# Schematic-easyEda.net
KiCad netlist of a schematic drawn in EasyEDA
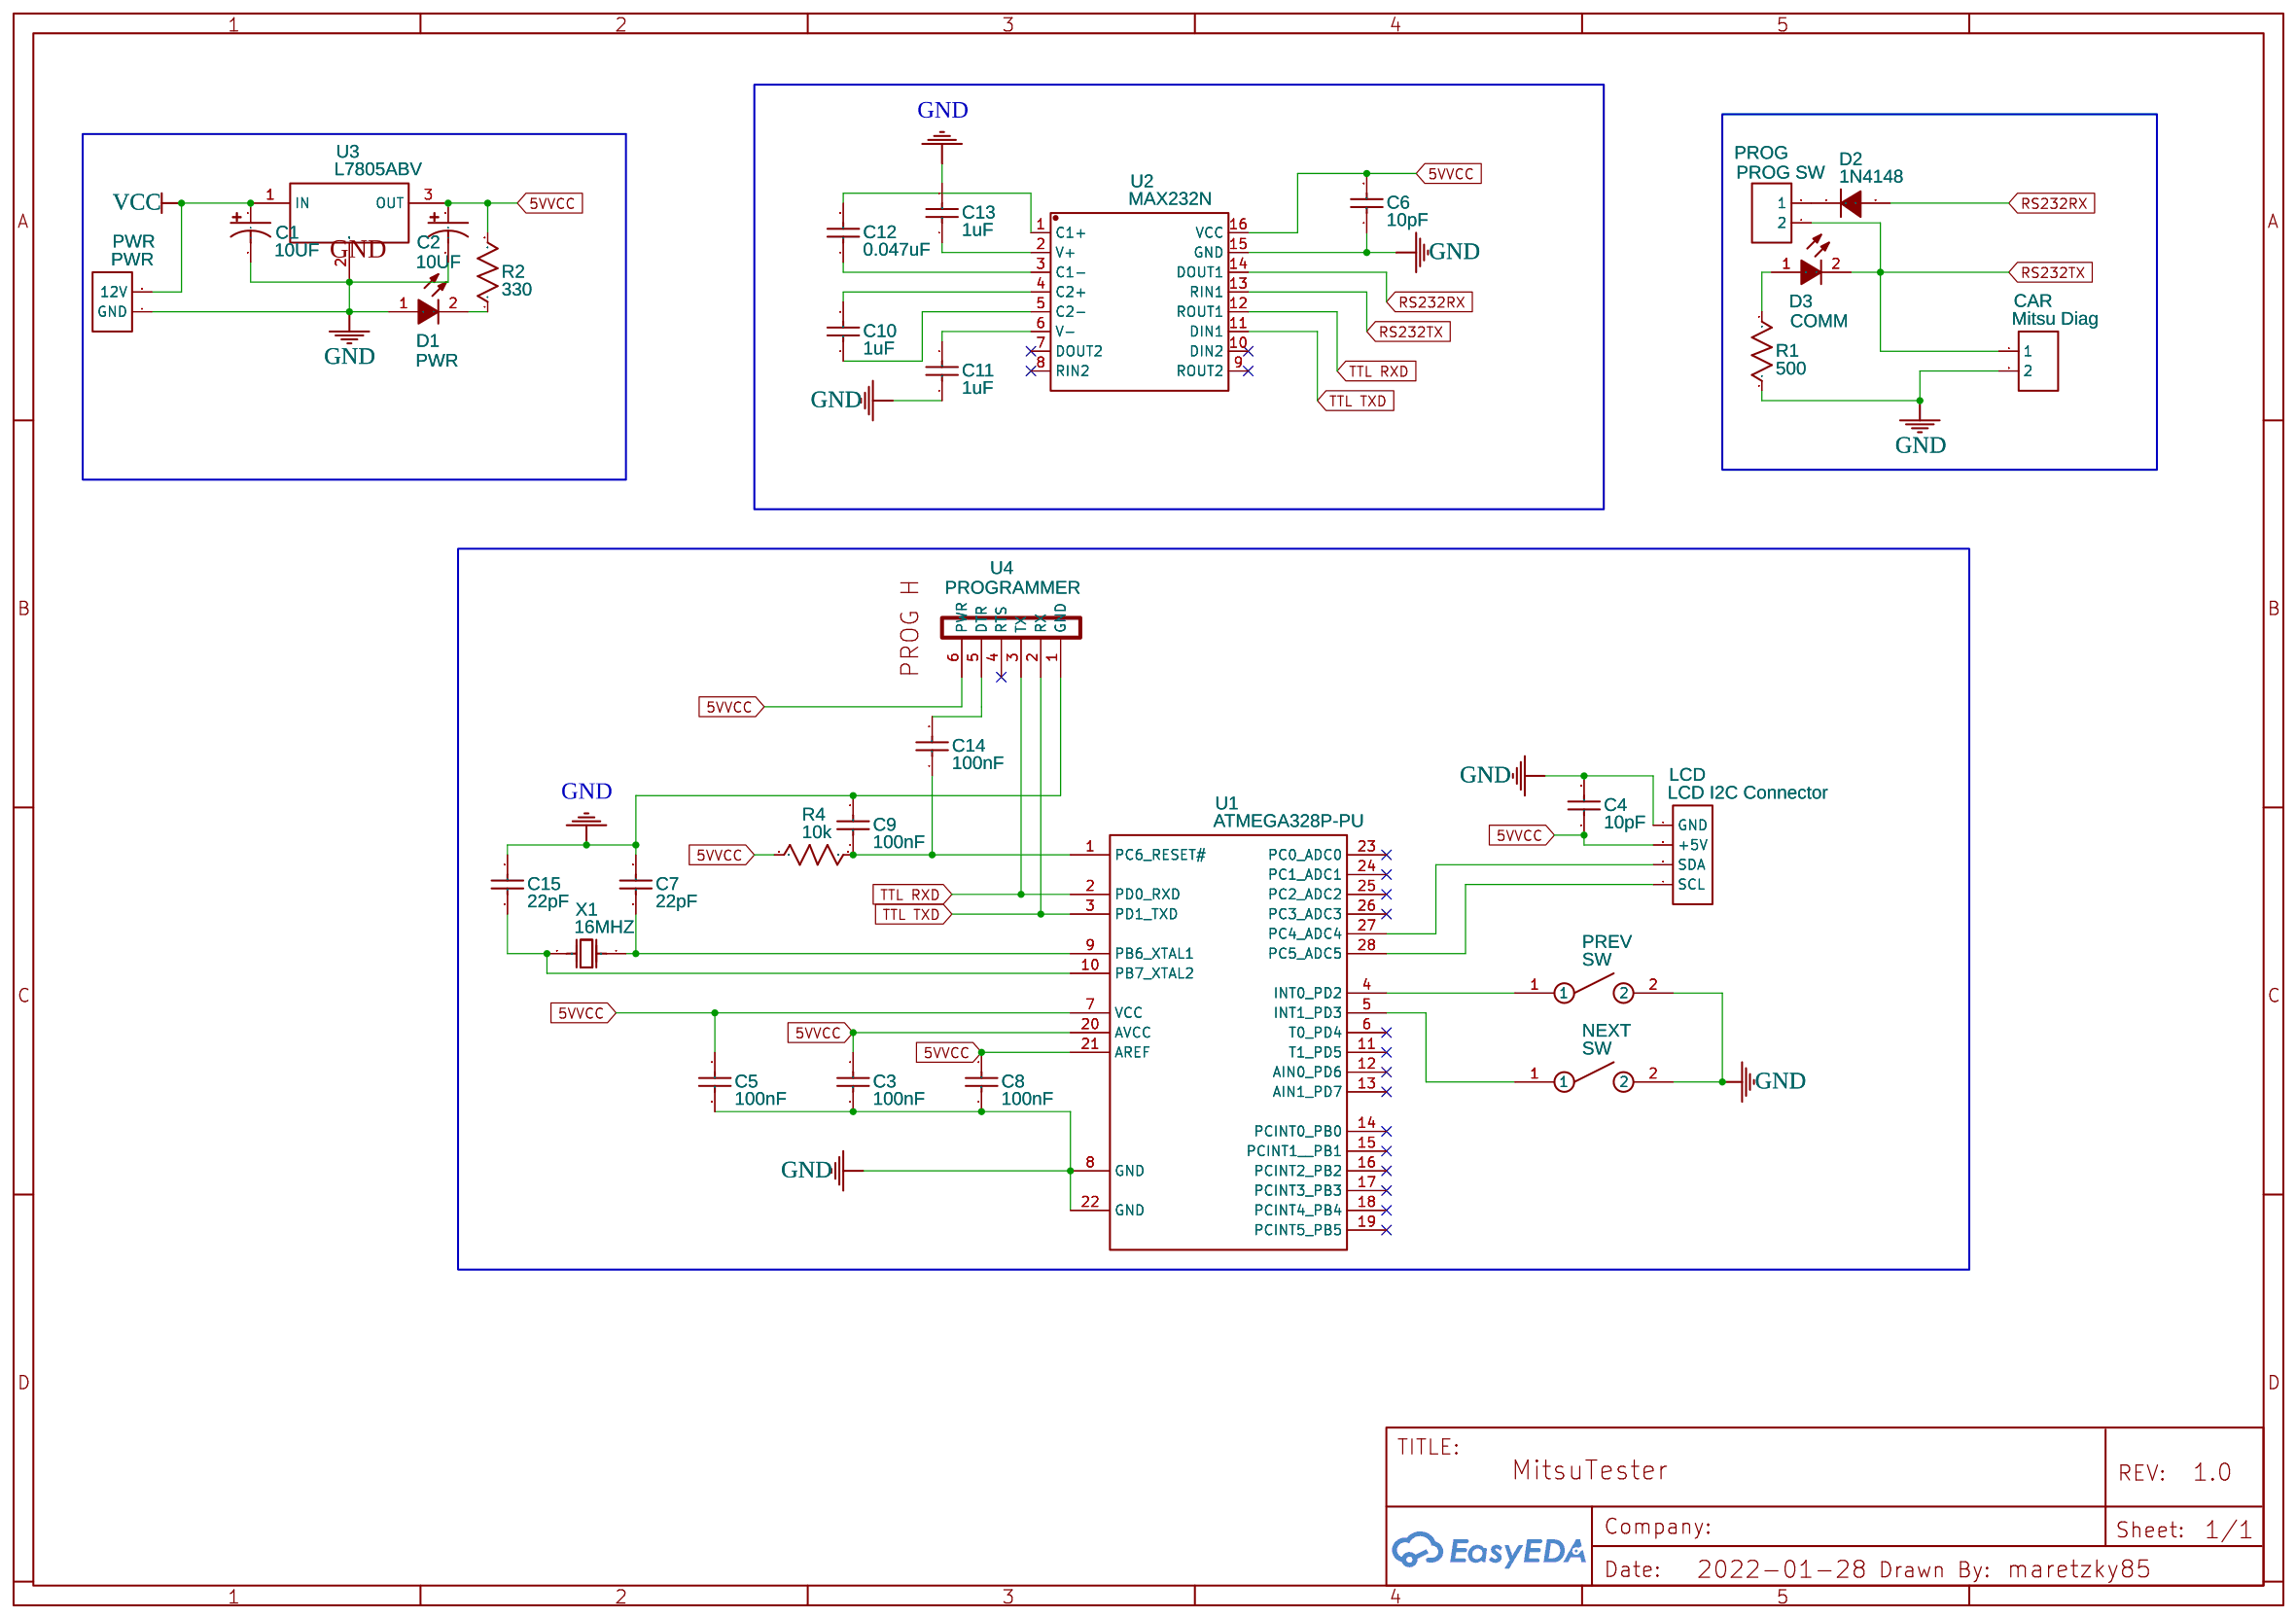
[diagram p0: schematic sheet]

(export (version "E")
  (design (tool "Eeschema 10.0.6"))
  (components
    (comp (ref "C1") (value "10UF") (libsource (lib "") (part "10UF-25V-20%(PTH)KIT")))
    (comp (ref "C2") (value "10UF") (libsource (lib "") (part "10UF-25V-20%(PTH)KIT")))
    (comp (ref "C3")
      (value "100nF")
      (fields
        (field (name "BOM_Manufacturer Part") "0.01 25V Ceramic capacitor")
        (field (name "BOM_Supplier Part") "C22320")
      )
      (libsource (lib "") (part "0.01 25V Ceramic capacitor"))
    )
    (comp (ref "C4")
      (value "10pF")
      (fields
        (field (name "BOM_Manufacturer Part") "0.01 25V Ceramic capacitor")
        (field (name "BOM_Supplier Part") "C22320")
      )
      (libsource (lib "") (part "0.01 25V Ceramic capacitor"))
    )
    (comp (ref "C5")
      (value "100nF")
      (fields
        (field (name "BOM_Manufacturer Part") "0.01 25V Ceramic capacitor")
        (field (name "BOM_Supplier Part") "C22320")
      )
      (libsource (lib "") (part "0.01 25V Ceramic capacitor"))
    )
    (comp (ref "C6")
      (value "10pF")
      (fields
        (field (name "BOM_Manufacturer Part") "0.01 25V Ceramic capacitor")
        (field (name "BOM_Supplier Part") "C22320")
      )
      (libsource (lib "") (part "0.01 25V Ceramic capacitor"))
    )
    (comp (ref "C7")
      (value "22pF")
      (fields
        (field (name "BOM_Manufacturer Part") "0.01 25V Ceramic capacitor")
        (field (name "BOM_Supplier Part") "C22320")
      )
      (libsource (lib "") (part "0.01 25V Ceramic capacitor"))
    )
    (comp (ref "C8")
      (value "100nF")
      (fields
        (field (name "BOM_Manufacturer Part") "0.01 25V Ceramic capacitor")
        (field (name "BOM_Supplier Part") "C22320")
      )
      (libsource (lib "") (part "0.01 25V Ceramic capacitor"))
    )
    (comp (ref "C9")
      (value "100nF")
      (fields
        (field (name "BOM_Manufacturer Part") "0.01 25V Ceramic capacitor")
        (field (name "BOM_Supplier Part") "C22320")
      )
      (libsource (lib "") (part "0.01 25V Ceramic capacitor"))
    )
    (comp (ref "C10")
      (value "1uF")
      (fields
        (field (name "BOM_Manufacturer Part") "0.01 25V Ceramic capacitor")
        (field (name "BOM_Supplier Part") "C22320")
      )
      (libsource (lib "") (part "0.01 25V Ceramic capacitor"))
    )
    (comp (ref "C11")
      (value "1uF")
      (fields
        (field (name "BOM_Manufacturer Part") "0.01 25V Ceramic capacitor")
        (field (name "BOM_Supplier Part") "C22320")
      )
      (libsource (lib "") (part "0.01 25V Ceramic capacitor"))
    )
    (comp (ref "C12")
      (value "0.047uF")
      (fields
        (field (name "BOM_Manufacturer Part") "0.01 25V Ceramic capacitor")
        (field (name "BOM_Supplier Part") "C22320")
      )
      (libsource (lib "") (part "0.01 25V Ceramic capacitor"))
    )
    (comp (ref "C13")
      (value "1uF")
      (fields
        (field (name "BOM_Manufacturer Part") "0.01 25V Ceramic capacitor")
        (field (name "BOM_Supplier Part") "C22320")
      )
      (libsource (lib "") (part "0.01 25V Ceramic capacitor"))
    )
    (comp (ref "C14")
      (value "100nF")
      (fields
        (field (name "BOM_Manufacturer Part") "0.01 25V Ceramic capacitor")
        (field (name "BOM_Supplier Part") "C22320")
      )
      (libsource (lib "") (part "0.01 25V Ceramic capacitor"))
    )
    (comp (ref "C15")
      (value "22pF")
      (fields
        (field (name "BOM_Manufacturer Part") "0.01 25V Ceramic capacitor")
        (field (name "BOM_Supplier Part") "C22320")
      )
      (libsource (lib "") (part "0.01 25V Ceramic capacitor"))
    )
    (comp (ref "CAR")
      (value "Mitsu Diag")
      (fields (field (name "BOM_Supplier Part") "C49661"))
      (libsource (lib "") (part "HDR-F-2.54_1x2_2"))
    )
    (comp (ref "D1")
      (value "PWR")
      (fields (field (name "BOM_Manufacturer Part") "5600") (field (name "BOM_Supplier Part") "L20325-ND"))
      (libsource (lib "") (part "3mm Green TH LED 5600"))
    )
    (comp (ref "D2")
      (value "1N4148")
      (fields (field (name "BOM_Manufacturer Part") "1N4007") (field (name "BOM_Supplier Part") "C106903"))
      (libsource (lib "") (part "2.54_DUMMY_DIODE"))
    )
    (comp (ref "D3")
      (value "COMM")
      (fields (field (name "BOM_Manufacturer Part") "5600") (field (name "BOM_Supplier Part") "L20325-ND"))
      (libsource (lib "") (part "3mm Green TH LED 5600"))
    )
    (comp (ref "LCD")
      (value "LCD I2C Connector")
      (fields (field (name "BOM_Supplier Part") "C225501"))
      (libsource (lib "") (part "HDR-F-2.54_1x4"))
    )
    (comp (ref "NEXT") (value "SW") (libsource (lib "") (part "SW_1")))
    (comp (ref "PREV") (value "SW") (libsource (lib "") (part "SW")))
    (comp (ref "PROG")
      (value "PROG SW")
      (fields (field (name "BOM_Supplier Part") "C49661"))
      (libsource (lib "") (part "HDR-F-2.54_1x2"))
    )
    (comp (ref "PWR")
      (value "PWR")
      (fields (field (name "BOM_Supplier Part") "C49661"))
      (libsource (lib "") (part "HDR-F-2.54_1x2_1"))
    )
    (comp (ref "R1") (value "500") (libsource (lib "") (part "R_AXIAL-0.3_US")))
    (comp (ref "R2") (value "330") (libsource (lib "") (part "R_AXIAL-0.3_US")))
    (comp (ref "R4") (value "10k") (libsource (lib "") (part "R_AXIAL-0.3_US_1")))
    (comp (ref "U1")
      (value "ATMEGA328P-PU")
      (fields (field (name "BOM_Supplier Part") "C33901"))
      (libsource (lib "") (part "ATMEGA328P-PU"))
    )
    (comp (ref "U2")
      (value "MAX232N")
      (fields (field (name "BOM_Supplier Part") "C353147"))
      (libsource (lib "") (part "MAX232N"))
    )
    (comp (ref "U3")
      (value "L7805ABV")
      (fields (field (name "BOM_Supplier Part") "C16807"))
      (libsource (lib "") (part "L7805ABV"))
    )
    (comp (ref "U4") (value "PROGRAMMER") (libsource (lib "") (part "6Pin Sip Header")))
    (comp (ref "X1")
      (value "16MHZ")
      (fields
        (field (name "BOM_Manufacturer Part") "49SAC16000202060")
        (field (name "BOM_Supplier Part") "C390745")
      )
      (libsource (lib "") (part "CRYSTAL 16MHZ"))
    )
  )
  (nets
    (net (code "1") (name "5VVCC") (class "Default")
      (node (ref "C2") (pin "1") (pinfunction "+_1") (pintype "unspecified"))
      (node (ref "C3") (pin "2") (pinfunction "2_2") (pintype "input"))
      (node (ref "C4") (pin "1") (pinfunction "1_1") (pintype "input"))
      (node (ref "C5") (pin "2") (pinfunction "2_2") (pintype "input"))
      (node (ref "C6") (pin "2") (pinfunction "2_2") (pintype "input"))
      (node (ref "C8") (pin "2") (pinfunction "2_2") (pintype "input"))
      (node (ref "LCD") (pin "2") (pinfunction "+5V_2") (pintype "unspecified"))
      (node (ref "R2") (pin "2") (pinfunction "2_2") (pintype "unspecified"))
      (node (ref "R4") (pin "1") (pinfunction "1_1") (pintype "unspecified"))
      (node (ref "U1") (pin "20") (pinfunction "AVCC_20") (pintype "passive"))
      (node (ref "U1") (pin "21") (pinfunction "AREF_21") (pintype "passive"))
      (node (ref "U1") (pin "7") (pinfunction "VCC_7") (pintype "passive"))
      (node (ref "U2") (pin "16") (pinfunction "VCC_16") (pintype "unspecified"))
      (node (ref "U3") (pin "3") (pinfunction "OUT_3") (pintype "passive"))
      (node (ref "U4") (pin "6") (pinfunction "PWR_6") (pintype "unspecified"))
    )
    (net (code "2") (name "GND") (class "Default")
      (node (ref "C1") (pin "2") (pinfunction "-_2") (pintype "unspecified"))
      (node (ref "C11") (pin "1") (pinfunction "1_1") (pintype "input"))
      (node (ref "C13") (pin "2") (pinfunction "2_2") (pintype "input"))
      (node (ref "C15") (pin "2") (pinfunction "2_2") (pintype "input"))
      (node (ref "C2") (pin "2") (pinfunction "-_2") (pintype "unspecified"))
      (node (ref "C3") (pin "1") (pinfunction "1_1") (pintype "input"))
      (node (ref "C4") (pin "2") (pinfunction "2_2") (pintype "input"))
      (node (ref "C5") (pin "1") (pinfunction "1_1") (pintype "input"))
      (node (ref "C6") (pin "1") (pinfunction "1_1") (pintype "input"))
      (node (ref "C7") (pin "2") (pinfunction "2_2") (pintype "input"))
      (node (ref "C8") (pin "1") (pinfunction "1_1") (pintype "input"))
      (node (ref "C9") (pin "2") (pinfunction "2_2") (pintype "input"))
      (node (ref "CAR") (pin "2") (pinfunction "2_2") (pintype "input"))
      (node (ref "D1") (pin "1") (pinfunction "A_1") (pintype "unspecified"))
      (node (ref "LCD") (pin "1") (pinfunction "GND_1") (pintype "unspecified"))
      (node (ref "NEXT") (pin "2") (pinfunction "2_2") (pintype "unspecified"))
      (node (ref "PREV") (pin "2") (pinfunction "2_2") (pintype "unspecified"))
      (node (ref "PWR") (pin "1") (pinfunction "GND_1") (pintype "input"))
      (node (ref "R1") (pin "1") (pinfunction "1_1") (pintype "unspecified"))
      (node (ref "U1") (pin "22") (pinfunction "GND_22") (pintype "passive"))
      (node (ref "U1") (pin "8") (pinfunction "GND_8") (pintype "passive"))
      (node (ref "U2") (pin "15") (pinfunction "GND_15") (pintype "unspecified"))
      (node (ref "U3") (pin "2") (pinfunction "GND_2") (pintype "passive"))
      (node (ref "U4") (pin "1") (pinfunction "GND_1") (pintype "unspecified"))
    )
    (net (code "3") (name "Net-(D1-K)") (class "Default")
      (node (ref "D1") (pin "2") (pinfunction "K_2") (pintype "unspecified"))
      (node (ref "R2") (pin "1") (pinfunction "1_1") (pintype "unspecified"))
    )
    (net (code "4") (name "Net-(D2-K)") (class "Default")
      (node (ref "D2") (pin "1") (pinfunction "K_1") (pintype "unspecified"))
      (node (ref "PROG") (pin "2") (pinfunction "1_2") (pintype "input"))
    )
    (net (code "5") (name "Net-(D3-A)") (class "Default")
      (node (ref "D3") (pin "1") (pinfunction "A_1") (pintype "unspecified"))
      (node (ref "R1") (pin "2") (pinfunction "2_2") (pintype "unspecified"))
    )
    (net (code "6") (name "Net-(LCD-SCL)") (class "Default")
      (node (ref "LCD") (pin "4") (pinfunction "SCL_4") (pintype "unspecified"))
      (node (ref "U1") (pin "28") (pinfunction "PC5_ADC5_28") (pintype "bidirectional"))
    )
    (net (code "7") (name "Net-(LCD-SDA)") (class "Default")
      (node (ref "LCD") (pin "3") (pinfunction "SDA_3") (pintype "unspecified"))
      (node (ref "U1") (pin "27") (pinfunction "PC4_ADC4_27") (pintype "bidirectional"))
    )
    (net (code "8") (name "Net-(U1-INT0_PD2)") (class "Default")
      (node (ref "PREV") (pin "1") (pinfunction "1_1") (pintype "unspecified"))
      (node (ref "U1") (pin "4") (pinfunction "INT0_PD2_4") (pintype "bidirectional"))
    )
    (net (code "9") (name "Net-(U1-INT1_PD3)") (class "Default")
      (node (ref "NEXT") (pin "1") (pinfunction "1_1") (pintype "unspecified"))
      (node (ref "U1") (pin "5") (pinfunction "INT1_PD3_5") (pintype "bidirectional"))
    )
    (net (code "10") (name "Net-(U1-PB6_XTAL1)") (class "Default")
      (node (ref "C7") (pin "1") (pinfunction "1_1") (pintype "input"))
      (node (ref "U1") (pin "9") (pinfunction "PB6_XTAL1_9") (pintype "bidirectional"))
      (node (ref "X1") (pin "1") (pinfunction "OSC1_1") (pintype "input"))
    )
    (net (code "11") (name "Net-(U1-PB7_XTAL2)") (class "Default")
      (node (ref "C15") (pin "1") (pinfunction "1_1") (pintype "input"))
      (node (ref "U1") (pin "10") (pinfunction "PB7_XTAL2_10") (pintype "bidirectional"))
      (node (ref "X1") (pin "2") (pinfunction "OSC2_2") (pintype "input"))
    )
    (net (code "12") (name "Net-(U1-PC6_RESET#)") (class "Default")
      (node (ref "C14") (pin "1") (pinfunction "1_1") (pintype "input"))
      (node (ref "C9") (pin "1") (pinfunction "1_1") (pintype "input"))
      (node (ref "R4") (pin "2") (pinfunction "2_2") (pintype "unspecified"))
      (node (ref "U1") (pin "1") (pinfunction "PC6_RESET#_1") (pintype "bidirectional"))
    )
    (net (code "13") (name "Net-(U2-C1+)") (class "Default")
      (node (ref "C12") (pin "2") (pinfunction "2_2") (pintype "input"))
      (node (ref "U2") (pin "1") (pinfunction "C1+_1") (pintype "unspecified"))
    )
    (net (code "14") (name "Net-(U2-C1-)") (class "Default")
      (node (ref "C12") (pin "1") (pinfunction "1_1") (pintype "input"))
      (node (ref "U2") (pin "3") (pinfunction "C1-_3") (pintype "unspecified"))
    )
    (net (code "15") (name "Net-(U2-C2+)") (class "Default")
      (node (ref "C10") (pin "2") (pinfunction "2_2") (pintype "input"))
      (node (ref "U2") (pin "4") (pinfunction "C2+_4") (pintype "unspecified"))
    )
    (net (code "16") (name "Net-(U2-C2-)") (class "Default")
      (node (ref "C10") (pin "1") (pinfunction "1_1") (pintype "input"))
      (node (ref "U2") (pin "5") (pinfunction "C2-_5") (pintype "unspecified"))
    )
    (net (code "17") (name "Net-(U2-V+)") (class "Default")
      (node (ref "C13") (pin "1") (pinfunction "1_1") (pintype "input"))
      (node (ref "U2") (pin "2") (pinfunction "V+_2") (pintype "unspecified"))
    )
    (net (code "18") (name "Net-(U2-V-)") (class "Default")
      (node (ref "C11") (pin "2") (pinfunction "2_2") (pintype "input"))
      (node (ref "U2") (pin "6") (pinfunction "V-_6") (pintype "unspecified"))
    )
    (net (code "19") (name "Net-(U4-DTR)") (class "Default")
      (node (ref "C14") (pin "2") (pinfunction "2_2") (pintype "input"))
      (node (ref "U4") (pin "5") (pinfunction "DTR_5") (pintype "unspecified"))
    )
    (net (code "20") (name "RS232RX") (class "Default")
      (node (ref "D2") (pin "2") (pinfunction "A_2") (pintype "unspecified"))
      (node (ref "U2") (pin "14") (pinfunction "DOUT1_14") (pintype "unspecified"))
    )
    (net (code "21") (name "RS232TX") (class "Default")
      (node (ref "CAR") (pin "1") (pinfunction "1_1") (pintype "input"))
      (node (ref "D3") (pin "2") (pinfunction "K_2") (pintype "unspecified"))
      (node (ref "PROG") (pin "1") (pinfunction "2_1") (pintype "input"))
      (node (ref "U2") (pin "13") (pinfunction "RIN1_13") (pintype "unspecified"))
    )
    (net (code "22") (name "TTL RXD") (class "Default")
      (node (ref "U1") (pin "2") (pinfunction "PD0_RXD_2") (pintype "bidirectional"))
      (node (ref "U2") (pin "12") (pinfunction "ROUT1_12") (pintype "unspecified"))
      (node (ref "U4") (pin "3") (pinfunction "TX_3") (pintype "unspecified"))
    )
    (net (code "23") (name "TTL TXD") (class "Default")
      (node (ref "U1") (pin "3") (pinfunction "PD1_TXD_3") (pintype "bidirectional"))
      (node (ref "U2") (pin "11") (pinfunction "DIN1_11") (pintype "unspecified"))
      (node (ref "U4") (pin "2") (pinfunction "RX_2") (pintype "unspecified"))
    )
    (net (code "24") (name "VCC") (class "Default")
      (node (ref "C1") (pin "1") (pinfunction "+_1") (pintype "unspecified"))
      (node (ref "PWR") (pin "2") (pinfunction "12V_2") (pintype "input"))
      (node (ref "U3") (pin "1") (pinfunction "IN_1") (pintype "passive"))
    )
    (net (code "25") (name "unconnected-(U1-AIN0_PD6-Pad12)") (class "Default")
      (node (ref "U1") (pin "12") (pinfunction "AIN0_PD6_12") (pintype "bidirectional+no_connect"))
    )
    (net (code "26") (name "unconnected-(U1-AIN1_PD7-Pad13)") (class "Default")
      (node (ref "U1") (pin "13") (pinfunction "AIN1_PD7_13") (pintype "bidirectional+no_connect"))
    )
    (net (code "27") (name "unconnected-(U1-PC0_ADC0-Pad23)") (class "Default")
      (node (ref "U1") (pin "23") (pinfunction "PC0_ADC0_23") (pintype "bidirectional+no_connect"))
    )
    (net (code "28") (name "unconnected-(U1-PC1_ADC1-Pad24)") (class "Default")
      (node (ref "U1") (pin "24") (pinfunction "PC1_ADC1_24") (pintype "bidirectional+no_connect"))
    )
    (net (code "29") (name "unconnected-(U1-PC2_ADC2-Pad25)") (class "Default")
      (node (ref "U1") (pin "25") (pinfunction "PC2_ADC2_25") (pintype "bidirectional+no_connect"))
    )
    (net (code "30") (name "unconnected-(U1-PC3_ADC3-Pad26)") (class "Default")
      (node (ref "U1") (pin "26") (pinfunction "PC3_ADC3_26") (pintype "bidirectional+no_connect"))
    )
    (net (code "31") (name "unconnected-(U1-PCINT0_PB0-Pad14)") (class "Default")
      (node (ref "U1") (pin "14") (pinfunction "PCINT0_PB0_14") (pintype "bidirectional+no_connect"))
    )
    (net (code "32") (name "unconnected-(U1-PCINT1__PB1-Pad15)") (class "Default")
      (node (ref "U1") (pin "15") (pinfunction "PCINT1__PB1_15") (pintype "bidirectional+no_connect"))
    )
    (net (code "33") (name "unconnected-(U1-PCINT2_PB2-Pad16)") (class "Default")
      (node (ref "U1") (pin "16") (pinfunction "PCINT2_PB2_16") (pintype "bidirectional+no_connect"))
    )
    (net (code "34") (name "unconnected-(U1-PCINT3_PB3-Pad17)") (class "Default")
      (node (ref "U1") (pin "17") (pinfunction "PCINT3_PB3_17") (pintype "bidirectional+no_connect"))
    )
    (net (code "35") (name "unconnected-(U1-PCINT4_PB4-Pad18)") (class "Default")
      (node (ref "U1") (pin "18") (pinfunction "PCINT4_PB4_18") (pintype "bidirectional+no_connect"))
    )
    (net (code "36") (name "unconnected-(U1-PCINT5_PB5-Pad19)") (class "Default")
      (node (ref "U1") (pin "19") (pinfunction "PCINT5_PB5_19") (pintype "bidirectional+no_connect"))
    )
    (net (code "37") (name "unconnected-(U1-T0_PD4-Pad6)") (class "Default")
      (node (ref "U1") (pin "6") (pinfunction "T0_PD4_6") (pintype "bidirectional+no_connect"))
    )
    (net (code "38") (name "unconnected-(U1-T1_PD5-Pad11)") (class "Default")
      (node (ref "U1") (pin "11") (pinfunction "T1_PD5_11") (pintype "bidirectional+no_connect"))
    )
    (net (code "39") (name "unconnected-(U2-DIN2-Pad10)") (class "Default")
      (node (ref "U2") (pin "10") (pinfunction "DIN2_10") (pintype "unspecified+no_connect"))
    )
    (net (code "40") (name "unconnected-(U2-DOUT2-Pad7)") (class "Default")
      (node (ref "U2") (pin "7") (pinfunction "DOUT2_7") (pintype "unspecified+no_connect"))
    )
    (net (code "41") (name "unconnected-(U2-RIN2-Pad8)") (class "Default")
      (node (ref "U2") (pin "8") (pinfunction "RIN2_8") (pintype "unspecified+no_connect"))
    )
    (net (code "42") (name "unconnected-(U2-ROUT2-Pad9)") (class "Default")
      (node (ref "U2") (pin "9") (pinfunction "ROUT2_9") (pintype "unspecified+no_connect"))
    )
    (net (code "43") (name "unconnected-(U4-RTS-Pad4)") (class "Default")
      (node (ref "U4") (pin "4") (pinfunction "RTS_4") (pintype "unspecified+no_connect"))
    )
  )
)
